# Sheet.net
KiCad netlist of a schematic drawn in Altium Designer
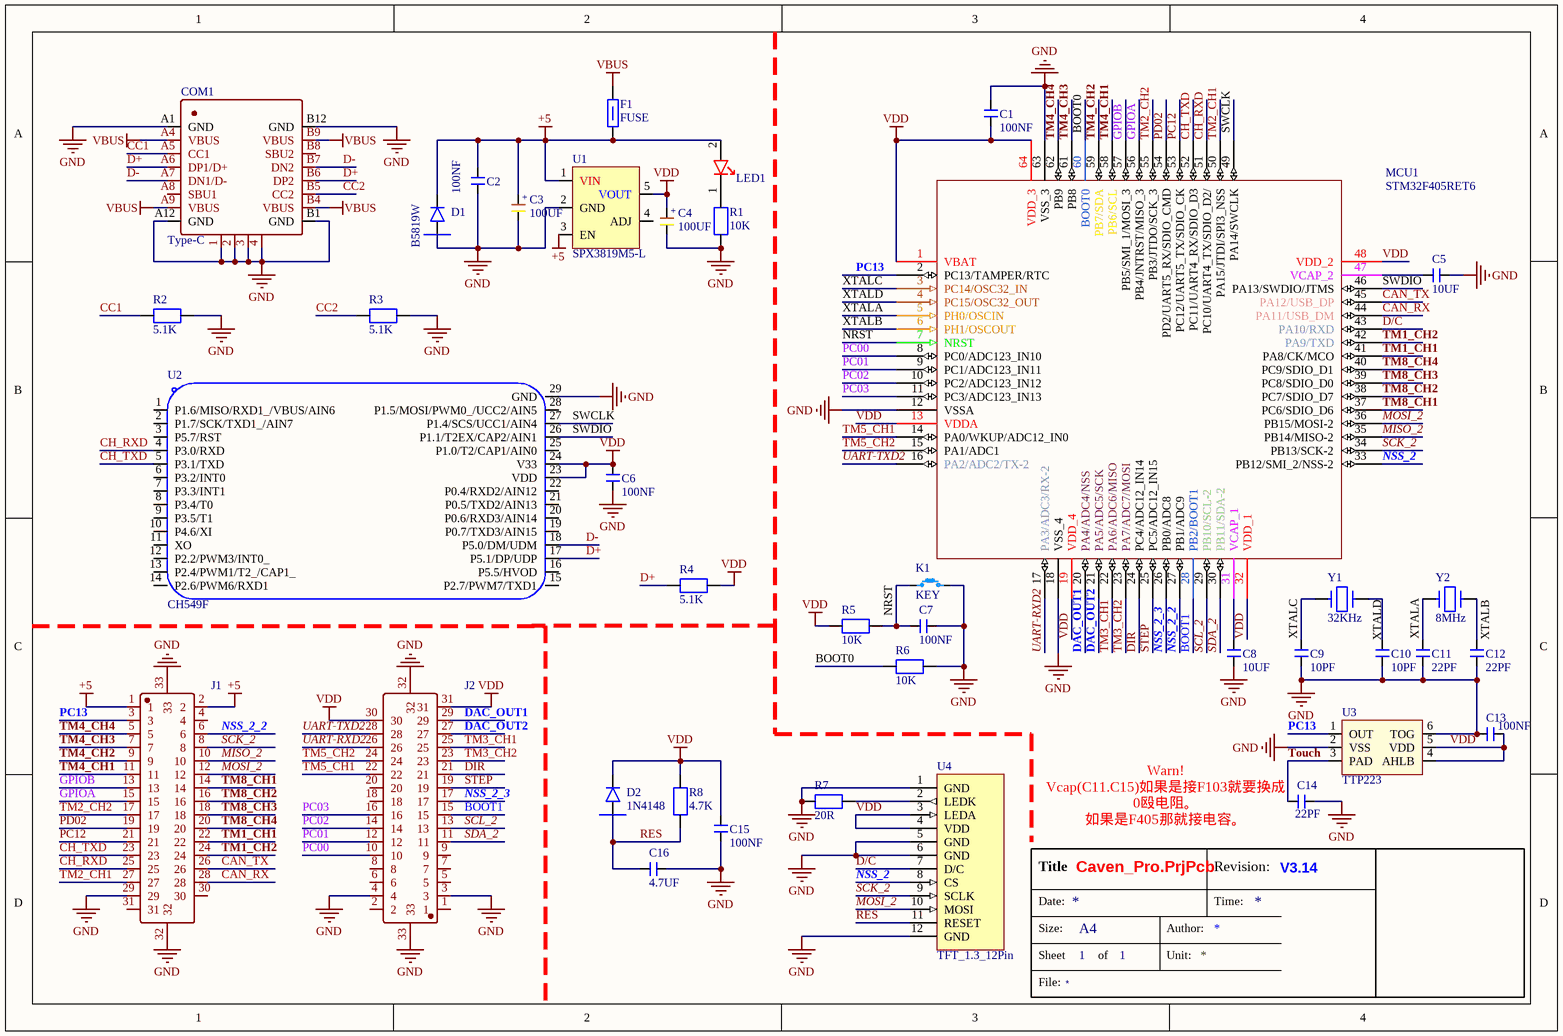
[diagram p0: Sheet.SchDoc]

(export (version "E")
  (design (tool "Eeschema 10.0.6"))
  (components
    (comp (ref "C1")
      (value "100NF")
      (footprint "CAP_0603")
      (description "CAP  12~50V")
      (libsource (lib "User") (part "CAP"))
    )
    (comp (ref "C2")
      (value "100NF")
      (footprint "CAP_0603")
      (description "CAP  12~50V")
      (libsource (lib "User") (part "CAP"))
    )
    (comp (ref "C3")
      (value "100UF")
      (footprint "CAP_3216_A")
      (description "CAP  6~12V  钽电容")
      (libsource (lib "User") (part "CAP_TA"))
    )
    (comp (ref "C4")
      (value "100UF")
      (footprint "CAP_3216_A")
      (description "CAP  6~12V  钽电容")
      (libsource (lib "User") (part "CAP_TA"))
    )
    (comp (ref "C5")
      (value "10UF")
      (footprint "CAP_0603")
      (description "CAP  12~50V")
      (libsource (lib "User") (part "CAP"))
    )
    (comp (ref "C6")
      (value "100NF")
      (footprint "CAP_0603")
      (description "CAP  12~50V")
      (libsource (lib "User") (part "CAP"))
    )
    (comp (ref "C7")
      (value "100NF")
      (footprint "CAP_0603")
      (description "CAP  12~50V")
      (libsource (lib "User") (part "CAP"))
    )
    (comp (ref "C8")
      (value "10UF")
      (footprint "CAP_0603")
      (description "CAP  12~50V")
      (libsource (lib "User") (part "CAP"))
    )
    (comp (ref "C9")
      (value "10PF")
      (footprint "CAP_0603")
      (description "CAP  12~50V")
      (libsource (lib "User") (part "CAP"))
    )
    (comp (ref "C10")
      (value "10PF")
      (footprint "CAP_0603")
      (description "CAP  12~50V")
      (libsource (lib "User") (part "CAP"))
    )
    (comp (ref "C11")
      (value "22PF")
      (footprint "CAP_0603")
      (description "CAP  12~50V")
      (libsource (lib "User") (part "CAP"))
    )
    (comp (ref "C12")
      (value "22PF")
      (footprint "CAP_0603")
      (description "CAP  12~50V")
      (libsource (lib "User") (part "CAP"))
    )
    (comp (ref "C13")
      (value "100NF")
      (footprint "CAP_0603")
      (description "CAP  12~50V")
      (libsource (lib "User") (part "CAP"))
    )
    (comp (ref "C14")
      (value "22PF")
      (footprint "CAP_0603")
      (description "CAP  12~50V")
      (libsource (lib "User") (part "CAP"))
    )
    (comp (ref "C15")
      (value "100NF")
      (footprint "CAP_0603")
      (description "CAP  12~50V")
      (libsource (lib "User") (part "CAP"))
    )
    (comp (ref "C16")
      (value "4.7UF")
      (footprint "CAP_0603")
      (description "CAP  12~50V")
      (libsource (lib "User") (part "CAP"))
    )
    (comp (ref "COM1")
      (value "Type-C")
      (footprint "USB-Type-C_16A")
      (description "USB")
      (libsource (lib "User") (part "USB-type_c"))
    )
    (comp (ref "D1")
      (value "B5819W")
      (footprint "DIODE_SOD123")
      (description "Diode_肖特基/二极管")
      (libsource (lib "User") (part "Diode-SM"))
    )
    (comp (ref "D2")
      (value "1N4148")
      (footprint "DIODE_SOD123")
      (description "Diode_肖特基/二极管")
      (libsource (lib "User") (part "Diode-SM"))
    )
    (comp (ref "F1") (value "FUSE") (footprint "Fuse_0603") (libsource (lib "User") (part "FUSE")))
    (comp (ref "J1")
      (value "31PIN")
      (footprint "BTB-DM3-31P")
      (description "BTB")
      (libsource (lib "User") (part "BTB_DF3_31Pin"))
    )
    (comp (ref "J2")
      (value "31PIN")
      (footprint "BTB-DM3-31P")
      (description "BTB")
      (libsource (lib "User") (part "BTB_DF3_31Pin"))
    )
    (comp (ref "K1")
      (value "KEY")
      (footprint "KEY_SMD")
      (description "Key")
      (libsource (lib "User") (part "KEY"))
    )
    (comp (ref "LED1")
      (value "LED_R/G/B/Y")
      (footprint "LED_0603_R")
      (description "LED")
      (libsource (lib "User") (part "LED_SMT"))
    )
    (comp (ref "MCU1")
      (value "STM32F405RET6")
      (footprint "LQFP_64_10X10")
      (description "MCU")
      (libsource (lib "User") (part "STM32f4_R"))
    )
    (comp (ref "R1")
      (value "10K")
      (footprint "RESC_0603_2")
      (description "RES 贴片")
      (libsource (lib "User") (part "RES_S"))
    )
    (comp (ref "R2")
      (value "5.1K")
      (footprint "RESC_0603_2")
      (description "RES 贴片")
      (libsource (lib "User") (part "RES"))
    )
    (comp (ref "R3")
      (value "5.1K")
      (footprint "RESC_0603_2")
      (description "RES 贴片")
      (libsource (lib "User") (part "RES"))
    )
    (comp (ref "R4")
      (value "5.1K")
      (footprint "RESC_0603_2")
      (description "RES 贴片")
      (libsource (lib "User") (part "RES"))
    )
    (comp (ref "R5")
      (value "10K")
      (footprint "RESC_0603_2")
      (description "RES 贴片")
      (libsource (lib "User") (part "RES_S"))
    )
    (comp (ref "R6")
      (value "10K")
      (footprint "RESC_0603_2")
      (description "RES 贴片")
      (libsource (lib "User") (part "RES_S"))
    )
    (comp (ref "R7")
      (value "20R")
      (footprint "RESC_0603_2")
      (description "RES 贴片")
      (libsource (lib "User") (part "RES_S"))
    )
    (comp (ref "R8")
      (value "4.7K")
      (footprint "RESC_0603_2")
      (description "RES 贴片")
      (libsource (lib "User") (part "RES_S"))
    )
    (comp (ref "U1")
      (value "SPX3819M5-L")
      (footprint "SOT23_5")
      (description "DC-DC   3.3V  500ma")
      (libsource (lib "User") (part "SPX3819M5-L"))
    )
    (comp (ref "U2")
      (value "CH549F")
      (footprint "QFN28-4X4L")
      (description "MCU")
      (fields (field (name "MANUFACTURER") "WCH(南京沁恒)"))
      (libsource (lib "User") (part "CH549F"))
    )
    (comp (ref "U3")
      (value "TTP223")
      (footprint "SOT-23-6")
      (description "触摸芯片")
      (libsource (lib "User") (part "TTP223"))
    )
    (comp (ref "U4")
      (value "TFT_1.3_12Pin")
      (footprint "LCD_1.3B")
      (description "ST7789V-SPI")
      (libsource (lib "User") (part "LCD_1.3   T"))
    )
    (comp (ref "Y1")
      (value "32KHz")
      (footprint "XTAL_SMD_3215")
      (description "CRYSTAL")
      (libsource (lib "User") (part "XTAL"))
    )
    (comp (ref "Y2")
      (value "8MHz")
      (footprint "XTAL-SMD5032-2P")
      (description "CRYSTAL")
      (libsource (lib "User") (part "XTAL"))
    )
  )
  (nets
    (net (code "1") (name "+5") (class "Default")
      (node (ref "C2") (pin "2") (pinfunction "0_2") (pintype "passive"))
      (node (ref "C3") (pin "1") (pinfunction "0_1") (pintype "passive"))
      (node (ref "D1") (pin "2") (pinfunction "N_2") (pintype "passive"))
      (node (ref "F1") (pin "1") (pinfunction "1_1") (pintype "passive"))
      (node (ref "J1") (pin "1") (pinfunction "1_1") (pintype "passive"))
      (node (ref "J1") (pin "2") (pinfunction "2_2") (pintype "passive"))
      (node (ref "LED1") (pin "2") (pinfunction "+_2") (pintype "passive"))
      (node (ref "U1") (pin "1") (pinfunction "VIN_1") (pintype "passive"))
      (node (ref "U1") (pin "3") (pinfunction "EN_3") (pintype "passive"))
    )
    (net (code "2") (name "/BOOT0") (class "Default")
      (node (ref "MCU1") (pin "60") (pinfunction "BOOT0_60") (pintype "passive"))
      (node (ref "R6") (pin "1") (pinfunction "1_1") (pintype "passive"))
    )
    (net (code "3") (name "/BOOT1") (class "Default")
      (node (ref "J2") (pin "15") (pinfunction "15_15") (pintype "passive"))
      (node (ref "MCU1") (pin "28") (pinfunction "PB2/BOOT1_28") (pintype "passive"))
    )
    (net (code "4") (name "/CAN_RX") (class "Default")
      (node (ref "J1") (pin "28") (pinfunction "28_28") (pintype "passive"))
      (node (ref "MCU1") (pin "44") (pinfunction "PA11/USB_DM_44") (pintype "bidirectional"))
    )
    (net (code "5") (name "/CAN_TX") (class "Default")
      (node (ref "J1") (pin "26") (pinfunction "26_26") (pintype "passive"))
      (node (ref "MCU1") (pin "45") (pinfunction "PA12/USB_DP_45") (pintype "bidirectional"))
    )
    (net (code "6") (name "/CC1") (class "Default")
      (node (ref "COM1") (pin "A5") (pinfunction "CC1_A5") (pintype "passive"))
      (node (ref "R2") (pin "2") (pinfunction "2_2") (pintype "passive"))
    )
    (net (code "7") (name "/CC2") (class "Default")
      (node (ref "COM1") (pin "B5") (pinfunction "CC2_B5") (pintype "passive"))
      (node (ref "R3") (pin "2") (pinfunction "2_2") (pintype "passive"))
    )
    (net (code "8") (name "/CH_RXD") (class "Default")
      (node (ref "J1") (pin "25") (pinfunction "25_25") (pintype "passive"))
      (node (ref "MCU1") (pin "51") (pinfunction "PC10/UART4_TX/SDIO_D2/_51") (pintype "bidirectional"))
      (node (ref "U2") (pin "4") (pinfunction "P3.0/RXD_4") (pintype "passive"))
    )
    (net (code "9") (name "/CH_TXD") (class "Default")
      (node (ref "J1") (pin "23") (pinfunction "23_23") (pintype "passive"))
      (node (ref "MCU1") (pin "52") (pinfunction "PC11/UART4_RX/SDIO_D3_52") (pintype "bidirectional"))
      (node (ref "U2") (pin "5") (pinfunction "P3.1/TXD_5") (pintype "passive"))
    )
    (net (code "10") (name "/D+") (class "Default")
      (node (ref "COM1") (pin "A6") (pinfunction "DP1/D+_A6") (pintype "passive"))
      (node (ref "COM1") (pin "B6") (pinfunction "DP2_B6") (pintype "passive"))
      (node (ref "R4") (pin "2") (pinfunction "2_2") (pintype "passive"))
      (node (ref "U2") (pin "17") (pinfunction "P5.1/DP/UDP_17") (pintype "passive"))
    )
    (net (code "11") (name "/D-") (class "Default")
      (node (ref "COM1") (pin "A7") (pinfunction "DN1/D-_A7") (pintype "passive"))
      (node (ref "COM1") (pin "B7") (pinfunction "DN2_B7") (pintype "passive"))
      (node (ref "U2") (pin "18") (pinfunction "P5.0/DM/UDM_18") (pintype "passive"))
    )
    (net (code "12") (name "/DAC_OUT1") (class "Default")
      (node (ref "J2") (pin "29") (pinfunction "29_29") (pintype "passive"))
      (node (ref "MCU1") (pin "20") (pinfunction "PA4/ADC4/NSS_20") (pintype "bidirectional"))
    )
    (net (code "13") (name "/DAC_OUT2") (class "Default")
      (node (ref "J2") (pin "27") (pinfunction "27_27") (pintype "passive"))
      (node (ref "MCU1") (pin "21") (pinfunction "PA5/ADC5/SCK_21") (pintype "bidirectional"))
    )
    (net (code "14") (name "/DIR") (class "Default")
      (node (ref "J2") (pin "21") (pinfunction "21_21") (pintype "passive"))
      (node (ref "MCU1") (pin "24") (pinfunction "PC4/ADC12_IN14_24") (pintype "bidirectional"))
    )
    (net (code "15") (name "/D{slash}C") (class "Default")
      (node (ref "MCU1") (pin "43") (pinfunction "PA10/RXD_43") (pintype "bidirectional"))
      (node (ref "U4") (pin "7") (pinfunction "D/C_7") (pintype "passive"))
    )
    (net (code "16") (name "/GPIOA") (class "Default")
      (node (ref "J1") (pin "15") (pinfunction "15_15") (pintype "passive"))
      (node (ref "MCU1") (pin "56") (pinfunction "PB4/JNTRST/MISO_3_56") (pintype "bidirectional"))
    )
    (net (code "17") (name "/GPIOB") (class "Default")
      (node (ref "J1") (pin "13") (pinfunction "13_13") (pintype "passive"))
      (node (ref "MCU1") (pin "57") (pinfunction "PB5/SMI_1/MOSI_3_57") (pintype "bidirectional"))
    )
    (net (code "18") (name "/MISO_2") (class "Default")
      (node (ref "J1") (pin "10") (pinfunction "10_10") (pintype "passive"))
      (node (ref "MCU1") (pin "35") (pinfunction "PB14/MISO-2_35") (pintype "bidirectional"))
    )
    (net (code "19") (name "/MOSI_2") (class "Default")
      (node (ref "J1") (pin "12") (pinfunction "12_12") (pintype "passive"))
      (node (ref "MCU1") (pin "36") (pinfunction "PB15/MOSI-2_36") (pintype "bidirectional"))
      (node (ref "U4") (pin "10") (pinfunction "MOSI_10") (pintype "input"))
    )
    (net (code "20") (name "/NRST") (class "Default")
      (node (ref "C7") (pin "2") (pinfunction "0_2") (pintype "passive"))
      (node (ref "K1") (pin "2") (pintype "passive"))
      (node (ref "MCU1") (pin "7") (pinfunction "NRST_7") (pintype "input"))
      (node (ref "R5") (pin "2") (pinfunction "2_2") (pintype "passive"))
    )
    (net (code "21") (name "/NSS_2") (class "Default")
      (node (ref "MCU1") (pin "33") (pinfunction "PB12/SMI_2/NSS-2_33") (pintype "bidirectional"))
      (node (ref "U4") (pin "8") (pinfunction "CS_8") (pintype "input"))
    )
    (net (code "22") (name "/NSS_2_2") (class "Default")
      (node (ref "J1") (pin "6") (pinfunction "6_6") (pintype "passive"))
      (node (ref "MCU1") (pin "27") (pinfunction "PB1/ADC9_27") (pintype "bidirectional"))
    )
    (net (code "23") (name "/NSS_2_3") (class "Default")
      (node (ref "J2") (pin "17") (pinfunction "17_17") (pintype "passive"))
      (node (ref "MCU1") (pin "26") (pinfunction "PB0/ADC8_26") (pintype "bidirectional"))
    )
    (net (code "24") (name "/PC00") (class "Default")
      (node (ref "J2") (pin "10") (pinfunction "10_10") (pintype "passive"))
      (node (ref "MCU1") (pin "8") (pinfunction "PC0/ADC123_IN10_8") (pintype "bidirectional"))
    )
    (net (code "25") (name "/PC01") (class "Default")
      (node (ref "J2") (pin "12") (pinfunction "12_12") (pintype "passive"))
      (node (ref "MCU1") (pin "9") (pinfunction "PC1/ADC123_IN11_9") (pintype "bidirectional"))
    )
    (net (code "26") (name "/PC02") (class "Default")
      (node (ref "J2") (pin "14") (pinfunction "14_14") (pintype "passive"))
      (node (ref "MCU1") (pin "10") (pinfunction "PC2/ADC123_IN12_10") (pintype "bidirectional"))
    )
    (net (code "27") (name "/PC03") (class "Default")
      (node (ref "J2") (pin "16") (pinfunction "16_16") (pintype "passive"))
      (node (ref "MCU1") (pin "11") (pinfunction "PC3/ADC123_IN13_11") (pintype "bidirectional"))
    )
    (net (code "28") (name "/PC12") (class "Default")
      (node (ref "J1") (pin "21") (pinfunction "21_21") (pintype "passive"))
      (node (ref "MCU1") (pin "53") (pinfunction "PC12/UART5_TX/SDIO_CK_53") (pintype "bidirectional"))
    )
    (net (code "29") (name "/PC13") (class "Default")
      (node (ref "J1") (pin "3") (pinfunction "3_3") (pintype "passive"))
      (node (ref "MCU1") (pin "2") (pinfunction "PC13/TAMPER/RTC_2") (pintype "bidirectional"))
      (node (ref "U3") (pin "1") (pinfunction "OUT_1") (pintype "passive"))
    )
    (net (code "30") (name "/PD02") (class "Default")
      (node (ref "J1") (pin "19") (pinfunction "19_19") (pintype "passive"))
      (node (ref "MCU1") (pin "54") (pinfunction "PD2/UART5_RX/SDIO_CMD_54") (pintype "bidirectional"))
    )
    (net (code "31") (name "/RES") (class "Default")
      (node (ref "C16") (pin "1") (pinfunction "0_1") (pintype "passive"))
      (node (ref "D2") (pin "1") (pinfunction "P_1") (pintype "passive"))
      (node (ref "R8") (pin "2") (pinfunction "2_2") (pintype "passive"))
      (node (ref "U4") (pin "11") (pinfunction "RESET_11") (pintype "passive"))
    )
    (net (code "32") (name "/SCK_2") (class "Default")
      (node (ref "J1") (pin "8") (pinfunction "8_8") (pintype "passive"))
      (node (ref "MCU1") (pin "34") (pinfunction "PB13/SCK-2_34") (pintype "bidirectional"))
      (node (ref "U4") (pin "9") (pinfunction "SCLK_9") (pintype "input"))
    )
    (net (code "33") (name "/SCL_2") (class "Default")
      (node (ref "J2") (pin "13") (pinfunction "13_13") (pintype "passive"))
      (node (ref "MCU1") (pin "29") (pinfunction "PB10/SCL-2_29") (pintype "bidirectional"))
    )
    (net (code "34") (name "/SDA_2") (class "Default")
      (node (ref "J2") (pin "11") (pinfunction "11_11") (pintype "passive"))
      (node (ref "MCU1") (pin "30") (pinfunction "PB11/SDA-2_30") (pintype "bidirectional"))
    )
    (net (code "35") (name "/STEP") (class "Default")
      (node (ref "J2") (pin "19") (pinfunction "19_19") (pintype "passive"))
      (node (ref "MCU1") (pin "25") (pinfunction "PC5/ADC12_IN15_25") (pintype "bidirectional"))
    )
    (net (code "36") (name "/SWCLK") (class "Default")
      (node (ref "MCU1") (pin "49") (pinfunction "PA14/SWCLK_49") (pintype "bidirectional"))
      (node (ref "U2") (pin "27") (pinfunction "P1.4/SCS/UCC1/AIN4_27") (pintype "passive"))
    )
    (net (code "37") (name "/SWDIO") (class "Default")
      (node (ref "MCU1") (pin "46") (pinfunction "PA13/SWDIO/JTMS_46") (pintype "bidirectional"))
      (node (ref "U2") (pin "26") (pinfunction "P1.1/T2EX/CAP2/AIN1_26") (pintype "passive"))
    )
    (net (code "38") (name "/TM1_CH1") (class "Default")
      (node (ref "J1") (pin "22") (pinfunction "22_22") (pintype "passive"))
      (node (ref "MCU1") (pin "41") (pinfunction "PA8/CK/MCO_41") (pintype "bidirectional"))
    )
    (net (code "39") (name "/TM1_CH2") (class "Default")
      (node (ref "J1") (pin "24") (pinfunction "24_24") (pintype "passive"))
      (node (ref "MCU1") (pin "42") (pinfunction "PA9/TXD_42") (pintype "bidirectional"))
    )
    (net (code "40") (name "/TM2_CH1") (class "Default")
      (node (ref "J1") (pin "27") (pinfunction "27_27") (pintype "passive"))
      (node (ref "MCU1") (pin "50") (pinfunction "PA15/JTDI/SPI3_NSS_50") (pintype "bidirectional"))
    )
    (net (code "41") (name "/TM2_CH2") (class "Default")
      (node (ref "J1") (pin "17") (pinfunction "17_17") (pintype "passive"))
      (node (ref "MCU1") (pin "55") (pinfunction "PB3/JTDO/SCK_3_55") (pintype "bidirectional"))
    )
    (net (code "42") (name "/TM3_CH1") (class "Default")
      (node (ref "J2") (pin "25") (pinfunction "25_25") (pintype "passive"))
      (node (ref "MCU1") (pin "22") (pinfunction "PA6/ADC6/MISO_22") (pintype "bidirectional"))
    )
    (net (code "43") (name "/TM3_CH2") (class "Default")
      (node (ref "J2") (pin "23") (pinfunction "23_23") (pintype "passive"))
      (node (ref "MCU1") (pin "23") (pinfunction "PA7/ADC7/MOSI_23") (pintype "bidirectional"))
    )
    (net (code "44") (name "/TM4_CH1") (class "Default")
      (node (ref "J1") (pin "11") (pinfunction "11_11") (pintype "passive"))
      (node (ref "MCU1") (pin "58") (pinfunction "PB6/SCL_58") (pintype "bidirectional"))
    )
    (net (code "45") (name "/TM4_CH2") (class "Default")
      (node (ref "J1") (pin "9") (pinfunction "9_9") (pintype "passive"))
      (node (ref "MCU1") (pin "59") (pinfunction "PB7/SDA_59") (pintype "bidirectional"))
    )
    (net (code "46") (name "/TM4_CH3") (class "Default")
      (node (ref "J1") (pin "7") (pinfunction "7_7") (pintype "passive"))
      (node (ref "MCU1") (pin "61") (pinfunction "PB8_61") (pintype "bidirectional"))
    )
    (net (code "47") (name "/TM4_CH4") (class "Default")
      (node (ref "J1") (pin "5") (pinfunction "5_5") (pintype "passive"))
      (node (ref "MCU1") (pin "62") (pinfunction "PB9_62") (pintype "bidirectional"))
    )
    (net (code "48") (name "/TM5_CH1") (class "Default")
      (node (ref "J2") (pin "22") (pinfunction "22_22") (pintype "passive"))
      (node (ref "MCU1") (pin "14") (pinfunction "PA0/WKUP/ADC12_IN0_14") (pintype "bidirectional"))
    )
    (net (code "49") (name "/TM5_CH2") (class "Default")
      (node (ref "J2") (pin "24") (pinfunction "24_24") (pintype "passive"))
      (node (ref "MCU1") (pin "15") (pinfunction "PA1/ADC1_15") (pintype "bidirectional"))
    )
    (net (code "50") (name "/TM8_CH1") (class "Default")
      (node (ref "J1") (pin "14") (pinfunction "14_14") (pintype "passive"))
      (node (ref "MCU1") (pin "37") (pinfunction "PC6/SDIO_D6_37") (pintype "bidirectional"))
    )
    (net (code "51") (name "/TM8_CH2") (class "Default")
      (node (ref "J1") (pin "16") (pinfunction "16_16") (pintype "passive"))
      (node (ref "MCU1") (pin "38") (pinfunction "PC7/SDIO_D7_38") (pintype "bidirectional"))
    )
    (net (code "52") (name "/TM8_CH3") (class "Default")
      (node (ref "J1") (pin "18") (pinfunction "18_18") (pintype "passive"))
      (node (ref "MCU1") (pin "39") (pinfunction "PC8/SDIO_D0_39") (pintype "bidirectional"))
    )
    (net (code "53") (name "/TM8_CH4") (class "Default")
      (node (ref "J1") (pin "20") (pinfunction "20_20") (pintype "passive"))
      (node (ref "MCU1") (pin "40") (pinfunction "PC9/SDIO_D1_40") (pintype "bidirectional"))
    )
    (net (code "54") (name "/Touch") (class "Default")
      (node (ref "C14") (pin "1") (pinfunction "0_1") (pintype "passive"))
      (node (ref "U3") (pin "3") (pinfunction "PAD_3") (pintype "passive"))
    )
    (net (code "55") (name "/UART-RXD2") (class "Default")
      (node (ref "J2") (pin "26") (pinfunction "26_26") (pintype "passive"))
      (node (ref "MCU1") (pin "17") (pinfunction "PA3/ADC3/RX-2_17") (pintype "bidirectional"))
    )
    (net (code "56") (name "/UART-TXD2") (class "Default")
      (node (ref "J2") (pin "28") (pinfunction "28_28") (pintype "passive"))
      (node (ref "MCU1") (pin "16") (pinfunction "PA2/ADC2/TX-2_16") (pintype "bidirectional"))
    )
    (net (code "57") (name "/XTALA") (class "Default")
      (node (ref "C11") (pin "1") (pinfunction "0_1") (pintype "passive"))
      (node (ref "MCU1") (pin "5") (pinfunction "PH0/OSCIN_5") (pintype "input"))
      (node (ref "Y2") (pin "2") (pinfunction "2_2") (pintype "passive"))
    )
    (net (code "58") (name "/XTALB") (class "Default")
      (node (ref "C12") (pin "1") (pinfunction "0_1") (pintype "passive"))
      (node (ref "MCU1") (pin "6") (pinfunction "PH1/OSCOUT_6") (pintype "input"))
      (node (ref "Y2") (pin "1") (pinfunction "1_1") (pintype "passive"))
    )
    (net (code "59") (name "/XTALC") (class "Default")
      (node (ref "C9") (pin "1") (pinfunction "0_1") (pintype "passive"))
      (node (ref "MCU1") (pin "3") (pinfunction "PC14/OSC32_IN_3") (pintype "input"))
      (node (ref "Y1") (pin "2") (pinfunction "2_2") (pintype "passive"))
    )
    (net (code "60") (name "/XTALD") (class "Default")
      (node (ref "C10") (pin "1") (pinfunction "0_1") (pintype "passive"))
      (node (ref "MCU1") (pin "4") (pinfunction "PC15/OSC32_OUT_4") (pintype "input"))
      (node (ref "Y1") (pin "1") (pinfunction "1_1") (pintype "passive"))
    )
    (net (code "61") (name "GND") (class "Default")
      (node (ref "C1") (pin "1") (pinfunction "0_1") (pintype "passive"))
      (node (ref "C10") (pin "2") (pinfunction "0_2") (pintype "passive"))
      (node (ref "C11") (pin "2") (pinfunction "0_2") (pintype "passive"))
      (node (ref "C12") (pin "2") (pinfunction "0_2") (pintype "passive"))
      (node (ref "C13") (pin "1") (pinfunction "0_1") (pintype "passive"))
      (node (ref "C14") (pin "2") (pinfunction "0_2") (pintype "passive"))
      (node (ref "C15") (pin "2") (pinfunction "0_2") (pintype "passive"))
      (node (ref "C16") (pin "2") (pinfunction "0_2") (pintype "passive"))
      (node (ref "C2") (pin "1") (pinfunction "0_1") (pintype "passive"))
      (node (ref "C3") (pin "2") (pinfunction "0_2") (pintype "passive"))
      (node (ref "C4") (pin "2") (pinfunction "0_2") (pintype "passive"))
      (node (ref "C5") (pin "1") (pinfunction "0_1") (pintype "passive"))
      (node (ref "C6") (pin "1") (pinfunction "0_1") (pintype "passive"))
      (node (ref "C7") (pin "1") (pinfunction "0_1") (pintype "passive"))
      (node (ref "C8") (pin "1") (pinfunction "0_1") (pintype "passive"))
      (node (ref "C9") (pin "2") (pinfunction "0_2") (pintype "passive"))
      (node (ref "COM1") (pin "1") (pinfunction "1_1") (pintype "passive"))
      (node (ref "COM1") (pin "2") (pinfunction "2_2") (pintype "passive"))
      (node (ref "COM1") (pin "3") (pinfunction "3_3") (pintype "passive"))
      (node (ref "COM1") (pin "4") (pinfunction "4_4") (pintype "passive"))
      (node (ref "COM1") (pin "A1") (pinfunction "GND_A1") (pintype "passive"))
      (node (ref "COM1") (pin "A12") (pinfunction "GND_A12") (pintype "passive"))
      (node (ref "COM1") (pin "B1") (pinfunction "GND_B1") (pintype "passive"))
      (node (ref "COM1") (pin "B12") (pinfunction "GND_B12") (pintype "passive"))
      (node (ref "D1") (pin "1") (pinfunction "P_1") (pintype "passive"))
      (node (ref "J1") (pin "29") (pinfunction "29_29") (pintype "passive"))
      (node (ref "J1") (pin "32") (pinfunction "32_32") (pintype "passive"))
      (node (ref "J1") (pin "33") (pinfunction "33_33") (pintype "passive"))
      (node (ref "J2") (pin "3") (pinfunction "3_3") (pintype "passive"))
      (node (ref "J2") (pin "32") (pinfunction "32_32") (pintype "passive"))
      (node (ref "J2") (pin "33") (pinfunction "33_33") (pintype "passive"))
      (node (ref "J2") (pin "4") (pinfunction "4_4") (pintype "passive"))
      (node (ref "K1") (pin "1") (pintype "passive"))
      (node (ref "MCU1") (pin "12") (pinfunction "VSSA_12") (pintype "power_in"))
      (node (ref "MCU1") (pin "18") (pinfunction "VSS_4_18") (pintype "power_in"))
      (node (ref "MCU1") (pin "63") (pinfunction "VSS_3_63") (pintype "power_in"))
      (node (ref "R1") (pin "1") (pinfunction "1_1") (pintype "passive"))
      (node (ref "R2") (pin "1") (pinfunction "1_1") (pintype "passive"))
      (node (ref "R3") (pin "1") (pinfunction "1_1") (pintype "passive"))
      (node (ref "R6") (pin "2") (pinfunction "2_2") (pintype "passive"))
      (node (ref "R7") (pin "1") (pinfunction "1_1") (pintype "passive"))
      (node (ref "U1") (pin "2") (pinfunction "GND_2") (pintype "passive"))
      (node (ref "U2") (pin "29") (pinfunction "GND_29") (pintype "passive"))
      (node (ref "U3") (pin "2") (pinfunction "VSS_2") (pintype "passive"))
      (node (ref "U3") (pin "6") (pinfunction "TOG_6") (pintype "passive"))
      (node (ref "U4") (pin "1") (pinfunction "GND_1") (pintype "passive"))
      (node (ref "U4") (pin "12") (pinfunction "GND_12") (pintype "passive"))
      (node (ref "U4") (pin "5") (pinfunction "GND_5") (pintype "passive"))
      (node (ref "U4") (pin "6") (pinfunction "GND_6") (pintype "passive"))
    )
    (net (code "62") (name "Net-(LED1--)") (class "Default")
      (node (ref "LED1") (pin "1") (pinfunction "-_1") (pintype "passive"))
      (node (ref "R1") (pin "2") (pinfunction "2_2") (pintype "passive"))
    )
    (net (code "63") (name "Net-(MCU1-VCAP_1)") (class "Default")
      (node (ref "C8") (pin "2") (pinfunction "0_2") (pintype "passive"))
      (node (ref "MCU1") (pin "31") (pinfunction "VCAP_1_31") (pintype "passive"))
    )
    (net (code "64") (name "Net-(MCU1-VCAP_2)") (class "Default")
      (node (ref "C5") (pin "2") (pinfunction "0_2") (pintype "passive"))
      (node (ref "MCU1") (pin "47") (pinfunction "VCAP_2_47") (pintype "passive"))
    )
    (net (code "65") (name "Net-(U4-LEDK)") (class "Default")
      (node (ref "R7") (pin "2") (pinfunction "2_2") (pintype "passive"))
      (node (ref "U4") (pin "2") (pinfunction "LEDK_2") (pintype "output"))
    )
    (net (code "66") (name "VBUS") (class "Default")
      (node (ref "COM1") (pin "A4") (pinfunction "VBUS_A4") (pintype "passive"))
      (node (ref "COM1") (pin "A9") (pinfunction "VBUS_A9") (pintype "passive"))
      (node (ref "COM1") (pin "B4") (pinfunction "VBUS_B4") (pintype "passive"))
      (node (ref "COM1") (pin "B9") (pinfunction "VBUS_B9") (pintype "passive"))
      (node (ref "F1") (pin "2") (pinfunction "2_2") (pintype "passive"))
    )
    (net (code "67") (name "VDD") (class "Default")
      (node (ref "C1") (pin "2") (pinfunction "0_2") (pintype "passive"))
      (node (ref "C13") (pin "2") (pinfunction "0_2") (pintype "passive"))
      (node (ref "C15") (pin "1") (pinfunction "0_1") (pintype "passive"))
      (node (ref "C4") (pin "1") (pinfunction "0_1") (pintype "passive"))
      (node (ref "C6") (pin "2") (pinfunction "0_2") (pintype "passive"))
      (node (ref "D2") (pin "2") (pinfunction "N_2") (pintype "passive"))
      (node (ref "J2") (pin "30") (pinfunction "30_30") (pintype "passive"))
      (node (ref "J2") (pin "31") (pinfunction "31_31") (pintype "passive"))
      (node (ref "MCU1") (pin "1") (pinfunction "VBAT_1") (pintype "power_in"))
      (node (ref "MCU1") (pin "13") (pinfunction "VDDA_13") (pintype "power_in"))
      (node (ref "MCU1") (pin "19") (pinfunction "VDD_4_19") (pintype "power_in"))
      (node (ref "MCU1") (pin "32") (pinfunction "VDD_1_32") (pintype "power_in"))
      (node (ref "MCU1") (pin "48") (pinfunction "VDD_2_48") (pintype "power_in"))
      (node (ref "MCU1") (pin "64") (pinfunction "VDD_3_64") (pintype "power_in"))
      (node (ref "R4") (pin "1") (pinfunction "1_1") (pintype "passive"))
      (node (ref "R5") (pin "1") (pinfunction "1_1") (pintype "passive"))
      (node (ref "R8") (pin "1") (pinfunction "1_1") (pintype "passive"))
      (node (ref "U1") (pin "5") (pinfunction "VOUT_5") (pintype "passive"))
      (node (ref "U2") (pin "23") (pinfunction "VDD_23") (pintype "passive"))
      (node (ref "U2") (pin "24") (pinfunction "V33_24") (pintype "passive"))
      (node (ref "U3") (pin "4") (pinfunction "AHLB_4") (pintype "passive"))
      (node (ref "U3") (pin "5") (pinfunction "VDD_5") (pintype "passive"))
      (node (ref "U4") (pin "3") (pinfunction "LEDA_3") (pintype "input"))
      (node (ref "U4") (pin "4") (pinfunction "VDD_4") (pintype "passive"))
    )
    (net (code "68") (name "unconnected-(COM1-SBU1-PadA8)") (class "Default")
      (node (ref "COM1") (pin "A8") (pinfunction "SBU1_A8") (pintype "passive"))
    )
    (net (code "69") (name "unconnected-(COM1-SBU2-PadB8)") (class "Default")
      (node (ref "COM1") (pin "B8") (pinfunction "SBU2_B8") (pintype "passive"))
    )
    (net (code "70") (name "unconnected-(J1-Pad4)") (class "Default")
      (node (ref "J1") (pin "4") (pinfunction "4_4") (pintype "passive"))
    )
    (net (code "71") (name "unconnected-(J1-Pad30)") (class "Default")
      (node (ref "J1") (pin "30") (pinfunction "30_30") (pintype "passive"))
    )
    (net (code "72") (name "unconnected-(J1-Pad31)") (class "Default")
      (node (ref "J1") (pin "31") (pinfunction "31_31") (pintype "passive"))
    )
    (net (code "73") (name "unconnected-(J2-Pad1)") (class "Default")
      (node (ref "J2") (pin "1") (pinfunction "1_1") (pintype "passive"))
    )
    (net (code "74") (name "unconnected-(J2-Pad2)") (class "Default")
      (node (ref "J2") (pin "2") (pinfunction "2_2") (pintype "passive"))
    )
    (net (code "75") (name "unconnected-(J2-Pad5)") (class "Default")
      (node (ref "J2") (pin "5") (pinfunction "5_5") (pintype "passive"))
    )
    (net (code "76") (name "unconnected-(J2-Pad6)") (class "Default")
      (node (ref "J2") (pin "6") (pinfunction "6_6") (pintype "passive"))
    )
    (net (code "77") (name "unconnected-(J2-Pad7)") (class "Default")
      (node (ref "J2") (pin "7") (pinfunction "7_7") (pintype "passive"))
    )
    (net (code "78") (name "unconnected-(J2-Pad8)") (class "Default")
      (node (ref "J2") (pin "8") (pinfunction "8_8") (pintype "passive"))
    )
    (net (code "79") (name "unconnected-(J2-Pad9)") (class "Default")
      (node (ref "J2") (pin "9") (pinfunction "9_9") (pintype "passive"))
    )
    (net (code "80") (name "unconnected-(J2-Pad18)") (class "Default")
      (node (ref "J2") (pin "18") (pinfunction "18_18") (pintype "passive"))
    )
    (net (code "81") (name "unconnected-(J2-Pad20)") (class "Default")
      (node (ref "J2") (pin "20") (pinfunction "20_20") (pintype "passive"))
    )
    (net (code "82") (name "unconnected-(U1-ADJ-Pad4)") (class "Default")
      (node (ref "U1") (pin "4") (pinfunction "ADJ_4") (pintype "passive"))
    )
    (net (code "83") (name "unconnected-(U2-P0.4{slash}RXD2{slash}AIN12-Pad22)") (class "Default")
      (node (ref "U2") (pin "22") (pinfunction "P0.4/RXD2/AIN12_22") (pintype "passive"))
    )
    (net (code "84") (name "unconnected-(U2-P0.5{slash}TXD2{slash}AIN13-Pad21)") (class "Default")
      (node (ref "U2") (pin "21") (pinfunction "P0.5/TXD2/AIN13_21") (pintype "passive"))
    )
    (net (code "85") (name "unconnected-(U2-P0.6{slash}RXD3{slash}AIN14-Pad20)") (class "Default")
      (node (ref "U2") (pin "20") (pinfunction "P0.6/RXD3/AIN14_20") (pintype "passive"))
    )
    (net (code "86") (name "unconnected-(U2-P0.7{slash}TXD3{slash}AIN15-Pad19)") (class "Default")
      (node (ref "U2") (pin "19") (pinfunction "P0.7/TXD3/AIN15_19") (pintype "passive"))
    )
    (net (code "87") (name "unconnected-(U2-P1.0{slash}T2{slash}CAP1{slash}AIN0-Pad25)") (class "Default")
      (node (ref "U2") (pin "25") (pinfunction "P1.0/T2/CAP1/AIN0_25") (pintype "passive"))
    )
    (net (code "88") (name "unconnected-(U2-P1.5{slash}MOSI{slash}PWM0_{slash}UCC2{slash}AIN5-Pad28)") (class "Default")
      (node (ref "U2") (pin "28") (pinfunction "P1.5/MOSI/PWM0_/UCC2/AIN5_28") (pintype "passive"))
    )
    (net (code "89") (name "unconnected-(U2-P1.6{slash}MISO{slash}RXD1_{slash}VBUS{slash}AIN6-Pad1)") (class "Default")
      (node (ref "U2") (pin "1") (pinfunction "P1.6/MISO/RXD1_/VBUS/AIN6_1") (pintype "passive"))
    )
    (net (code "90") (name "unconnected-(U2-P1.7{slash}SCK{slash}TXD1_{slash}AIN7-Pad2)") (class "Default")
      (node (ref "U2") (pin "2") (pinfunction "P1.7/SCK/TXD1_/AIN7_2") (pintype "passive"))
    )
    (net (code "91") (name "unconnected-(U2-P2.2{slash}PWM3{slash}INT0_-Pad12)") (class "Default")
      (node (ref "U2") (pin "12") (pinfunction "P2.2/PWM3/INT0__12") (pintype "passive"))
    )
    (net (code "92") (name "unconnected-(U2-P2.4{slash}PWM1{slash}T2_{slash}CAP1_-Pad13)") (class "Default")
      (node (ref "U2") (pin "13") (pinfunction "P2.4/PWM1/T2_/CAP1__13") (pintype "passive"))
    )
    (net (code "93") (name "unconnected-(U2-P2.6{slash}PWM6{slash}RXD1-Pad14)") (class "Default")
      (node (ref "U2") (pin "14") (pinfunction "P2.6/PWM6/RXD1_14") (pintype "passive"))
    )
    (net (code "94") (name "unconnected-(U2-P2.7{slash}PWM7{slash}TXD1-Pad15)") (class "Default")
      (node (ref "U2") (pin "15") (pinfunction "P2.7/PWM7/TXD1_15") (pintype "passive"))
    )
    (net (code "95") (name "unconnected-(U2-P3.2{slash}INT0-Pad6)") (class "Default")
      (node (ref "U2") (pin "6") (pinfunction "P3.2/INT0_6") (pintype "passive"))
    )
    (net (code "96") (name "unconnected-(U2-P3.3{slash}INT1-Pad7)") (class "Default")
      (node (ref "U2") (pin "7") (pinfunction "P3.3/INT1_7") (pintype "passive"))
    )
    (net (code "97") (name "unconnected-(U2-P3.4{slash}T0-Pad8)") (class "Default")
      (node (ref "U2") (pin "8") (pinfunction "P3.4/T0_8") (pintype "passive"))
    )
    (net (code "98") (name "unconnected-(U2-P3.5{slash}T1-Pad9)") (class "Default")
      (node (ref "U2") (pin "9") (pinfunction "P3.5/T1_9") (pintype "passive"))
    )
    (net (code "99") (name "unconnected-(U2-P4.6{slash}XI-Pad10)") (class "Default")
      (node (ref "U2") (pin "10") (pinfunction "P4.6/XI_10") (pintype "passive"))
    )
    (net (code "100") (name "unconnected-(U2-P5.5{slash}HVOD-Pad16)") (class "Default")
      (node (ref "U2") (pin "16") (pinfunction "P5.5/HVOD_16") (pintype "passive"))
    )
    (net (code "101") (name "unconnected-(U2-P5.7{slash}RST-Pad3)") (class "Default")
      (node (ref "U2") (pin "3") (pinfunction "P5.7/RST_3") (pintype "passive"))
    )
    (net (code "102") (name "unconnected-(U2-XO-Pad11)") (class "Default")
      (node (ref "U2") (pin "11") (pinfunction "XO_11") (pintype "passive"))
    )
  )
)
